# DP_UART_CH340G.net
KiCad netlist of a schematic drawn in Altium Designer
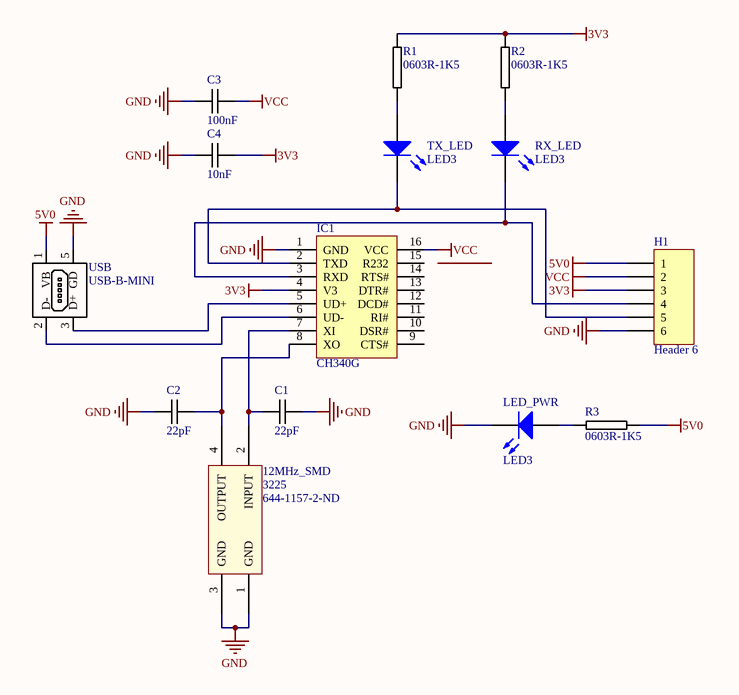
[diagram p0: DP_UART_CH340G.SchDoc]

(export (version "E")
  (design (tool "Eeschema 10.0.6"))
  (components
    (comp (ref "12MHz_SMD")
      (value "3225")
      (footprint "XTAL 3225")
      (fields (field (name "SUPPLIER PART NUMBER 1") "644-1157-2-ND"))
      (libsource (lib "RVA_Reference_Crystal Oscillator_SMD") (part "3225 Quartz"))
    )
    (comp (ref "C1")
      (value "22pF")
      (footprint "0603C-GENERIC")
      (description "CAPACITOR 0603 CERAMIC")
      (fields (field (name "TOLERANCE") "±5%") (field (name "MANUFACTURER PART NUMBER") "ECJ-1VC1H220J"))
      (libsource (lib "RVA_Passives_Capacitors_0603") (part "Passives_Capacitors_0603_22PF-50V-C0G-PAN"))
    )
    (comp (ref "C2")
      (value "22pF")
      (footprint "0603C-GENERIC")
      (description "CAPACITOR 0603 CERAMIC")
      (fields (field (name "TOLERANCE") "±5%") (field (name "MANUFACTURER PART NUMBER") "ECJ-1VC1H220J"))
      (libsource (lib "RVA_Passives_Capacitors_0603") (part "Passives_Capacitors_0603_22PF-50V-C0G-PAN"))
    )
    (comp (ref "C3")
      (value "100nF")
      (footprint "0603C-GENERIC")
      (description "CAPACITOR 0603 CERAMIC")
      (fields
        (field (name "MANUFACTURER PART NUMBER") "C1608X7R1E104K")
        (field (name "MANUFACTURER") "TDK Corporation")
      )
      (libsource (lib "RVA_Passives_Capacitors_0603") (part "Passives_Capacitors_0603_100NF-25V-X7R-TDK"))
    )
    (comp (ref "C4")
      (value "10nF")
      (footprint "0603C-GENERIC")
      (description "CAPACITOR 0603 CERAMIC")
      (fields
        (field (name "MANUFACTURER PART NUMBER") "GRM188R71H103KA01D")
        (field (name "MANUFACTURER") "Murata Electronics North America")
      )
      (libsource (lib "RVA_Passives_Capacitors_0603") (part "Passives_Capacitors_0603_10NF-50V-X7R-MUR"))
    )
    (comp (ref "H1")
      (value "Header 6")
      (footprint "HDR1X6")
      (description "Header, 6-Pin")
      (fields (field (name "PUBLISHER") "Altium Limited"))
      (libsource (lib "Miscellaneous Connectors") (part "Header 6"))
    )
    (comp (ref "IC1") (value "CH340G") (footprint "SO16") (libsource (lib "CH340") (part "CH340G")))
    (comp (ref "LED_PWR")
      (value "LED3")
      (footprint "3.5X2.8X1.9")
      (description "Typical BLUE SiC LED")
      (fields (field (name "PUBLISHER") "Altium Limited"))
      (libsource (lib "Miscellaneous Devices") (part "LED3"))
    )
    (comp (ref "R1")
      (value "0603R-1K5")
      (footprint "0603R-1k5")
      (description "GENERIC RESISTOR 0603")
      (fields (field (name "MANUFACTURER PART NUMBER") "RMCF 1/16 15K 1% R") (field (name "TOLERANCE") "±1%"))
      (libsource (lib "RVA_Passives_Resistors_0603") (part "0603R-1K5"))
    )
    (comp (ref "R2")
      (value "0603R-1K5")
      (footprint "0603R-1k5")
      (description "GENERIC RESISTOR 0603")
      (fields (field (name "MANUFACTURER PART NUMBER") "RMCF 1/16 15K 1% R") (field (name "TOLERANCE") "±1%"))
      (libsource (lib "RVA_Passives_Resistors_0603") (part "0603R-1K5"))
    )
    (comp (ref "R3")
      (value "0603R-1K5")
      (footprint "0603R-1k5")
      (description "GENERIC RESISTOR 0603")
      (fields (field (name "MANUFACTURER PART NUMBER") "RMCF 1/16 15K 1% R") (field (name "TOLERANCE") "±1%"))
      (libsource (lib "RVA_Passives_Resistors_0603") (part "0603R-1K5"))
    )
    (comp (ref "RX_LED")
      (value "LED3")
      (footprint "3.5X2.8X1.9")
      (description "Typical BLUE SiC LED")
      (fields (field (name "PUBLISHER") "Altium Limited"))
      (libsource (lib "Miscellaneous Devices") (part "LED3"))
    )
    (comp (ref "TX_LED")
      (value "LED3")
      (footprint "3.5X2.8X1.9")
      (description "Typical BLUE SiC LED")
      (fields (field (name "PUBLISHER") "Altium Limited"))
      (libsource (lib "Miscellaneous Devices") (part "LED3"))
    )
    (comp (ref "USB")
      (value "USB-B-MINI")
      (footprint "USB-MINI-B")
      (description "MINI USB B DEVICE CONNECTOR")
      (libsource (lib "RVA_Connector_USB_THT") (part "Connector_USB_THT_USB-B-MINI"))
    )
  )
  (nets
    (net (code "1") (name "3V3") (class "Default")
      (node (ref "C4") (pin "2") (pintype "passive"))
      (node (ref "H1") (pin "3") (pinfunction "3_3") (pintype "passive"))
      (node (ref "IC1") (pin "4") (pinfunction "V3_4") (pintype "passive"))
      (node (ref "R1") (pin "1") (pintype "passive"))
      (node (ref "R2") (pin "1") (pintype "passive"))
    )
    (net (code "2") (name "5V0") (class "Default")
      (node (ref "H1") (pin "1") (pinfunction "1_1") (pintype "passive"))
      (node (ref "R3") (pin "1") (pintype "passive"))
      (node (ref "USB") (pin "1") (pinfunction "VB_1") (pintype "passive"))
    )
    (net (code "3") (name "GND") (class "Default")
      (node (ref "12MHz_SMD") (pin "1") (pinfunction "GND_1") (pintype "passive"))
      (node (ref "12MHz_SMD") (pin "3") (pinfunction "GND_3") (pintype "passive"))
      (node (ref "C1") (pin "2") (pintype "passive"))
      (node (ref "C2") (pin "1") (pintype "passive"))
      (node (ref "C3") (pin "1") (pintype "passive"))
      (node (ref "C4") (pin "1") (pintype "passive"))
      (node (ref "H1") (pin "6") (pinfunction "6_6") (pintype "passive"))
      (node (ref "IC1") (pin "1") (pinfunction "GND_1") (pintype "passive"))
      (node (ref "LED_PWR") (pin "2") (pinfunction "K_2") (pintype "passive"))
      (node (ref "USB") (pin "5") (pinfunction "GD_5") (pintype "passive"))
    )
    (net (code "4") (name "Net-(12MHz_SMD-INPUT)") (class "Default")
      (node (ref "12MHz_SMD") (pin "2") (pinfunction "INPUT_2") (pintype "passive"))
      (node (ref "C1") (pin "1") (pintype "passive"))
      (node (ref "IC1") (pin "7") (pinfunction "XI_7") (pintype "passive"))
    )
    (net (code "5") (name "Net-(12MHz_SMD-OUTPUT)") (class "Default")
      (node (ref "12MHz_SMD") (pin "4") (pinfunction "OUTPUT_4") (pintype "passive"))
      (node (ref "C2") (pin "2") (pintype "passive"))
      (node (ref "IC1") (pin "8") (pinfunction "XO_8") (pintype "passive"))
    )
    (net (code "6") (name "Net-(IC1-RXD)") (class "Default")
      (node (ref "H1") (pin "4") (pinfunction "4_4") (pintype "passive"))
      (node (ref "IC1") (pin "3") (pinfunction "RXD_3") (pintype "passive"))
      (node (ref "RX_LED") (pin "2") (pinfunction "K_2") (pintype "passive"))
    )
    (net (code "7") (name "Net-(IC1-TXD)") (class "Default")
      (node (ref "H1") (pin "5") (pinfunction "5_5") (pintype "passive"))
      (node (ref "IC1") (pin "2") (pinfunction "TXD_2") (pintype "passive"))
      (node (ref "TX_LED") (pin "2") (pinfunction "K_2") (pintype "passive"))
    )
    (net (code "8") (name "Net-(IC1-UD+)") (class "Default")
      (node (ref "IC1") (pin "5") (pinfunction "UD+_5") (pintype "passive"))
      (node (ref "USB") (pin "3") (pinfunction "D+_3") (pintype "passive"))
    )
    (net (code "9") (name "Net-(IC1-UD-)") (class "Default")
      (node (ref "IC1") (pin "6") (pinfunction "UD-_6") (pintype "passive"))
      (node (ref "USB") (pin "2") (pinfunction "D-_2") (pintype "passive"))
    )
    (net (code "10") (name "Net-(LED_PWR-A)") (class "Default")
      (node (ref "LED_PWR") (pin "1") (pinfunction "A_1") (pintype "passive"))
      (node (ref "R3") (pin "2") (pintype "passive"))
    )
    (net (code "11") (name "Net-(RX_LED-A)") (class "Default")
      (node (ref "R2") (pin "2") (pintype "passive"))
      (node (ref "RX_LED") (pin "1") (pinfunction "A_1") (pintype "passive"))
    )
    (net (code "12") (name "Net-(TX_LED-A)") (class "Default")
      (node (ref "R1") (pin "2") (pintype "passive"))
      (node (ref "TX_LED") (pin "1") (pinfunction "A_1") (pintype "passive"))
    )
    (net (code "13") (name "VCC") (class "Default")
      (node (ref "C3") (pin "2") (pintype "passive"))
      (node (ref "H1") (pin "2") (pinfunction "2_2") (pintype "passive"))
      (node (ref "IC1") (pin "16") (pinfunction "VCC_16") (pintype "passive"))
    )
    (net (code "14") (name "unconnected-(IC1-CTS#-Pad9)") (class "Default")
      (node (ref "IC1") (pin "9") (pinfunction "CTS#_9") (pintype "passive"))
    )
    (net (code "15") (name "unconnected-(IC1-DCD#-Pad12)") (class "Default")
      (node (ref "IC1") (pin "12") (pinfunction "DCD#_12") (pintype "passive"))
    )
    (net (code "16") (name "unconnected-(IC1-DSR#-Pad10)") (class "Default")
      (node (ref "IC1") (pin "10") (pinfunction "DSR#_10") (pintype "passive"))
    )
    (net (code "17") (name "unconnected-(IC1-DTR#-Pad13)") (class "Default")
      (node (ref "IC1") (pin "13") (pinfunction "DTR#_13") (pintype "passive"))
    )
    (net (code "18") (name "unconnected-(IC1-R232-Pad15)") (class "Default")
      (node (ref "IC1") (pin "15") (pinfunction "R232_15") (pintype "passive"))
    )
    (net (code "19") (name "unconnected-(IC1-RI#-Pad11)") (class "Default")
      (node (ref "IC1") (pin "11") (pinfunction "RI#_11") (pintype "passive"))
    )
    (net (code "20") (name "unconnected-(IC1-RTS#-Pad14)") (class "Default")
      (node (ref "IC1") (pin "14") (pinfunction "RTS#_14") (pintype "passive"))
    )
  )
)
